# 2225B_VumetreFrequenciel.net
KiCad netlist of a schematic drawn in Altium Designer
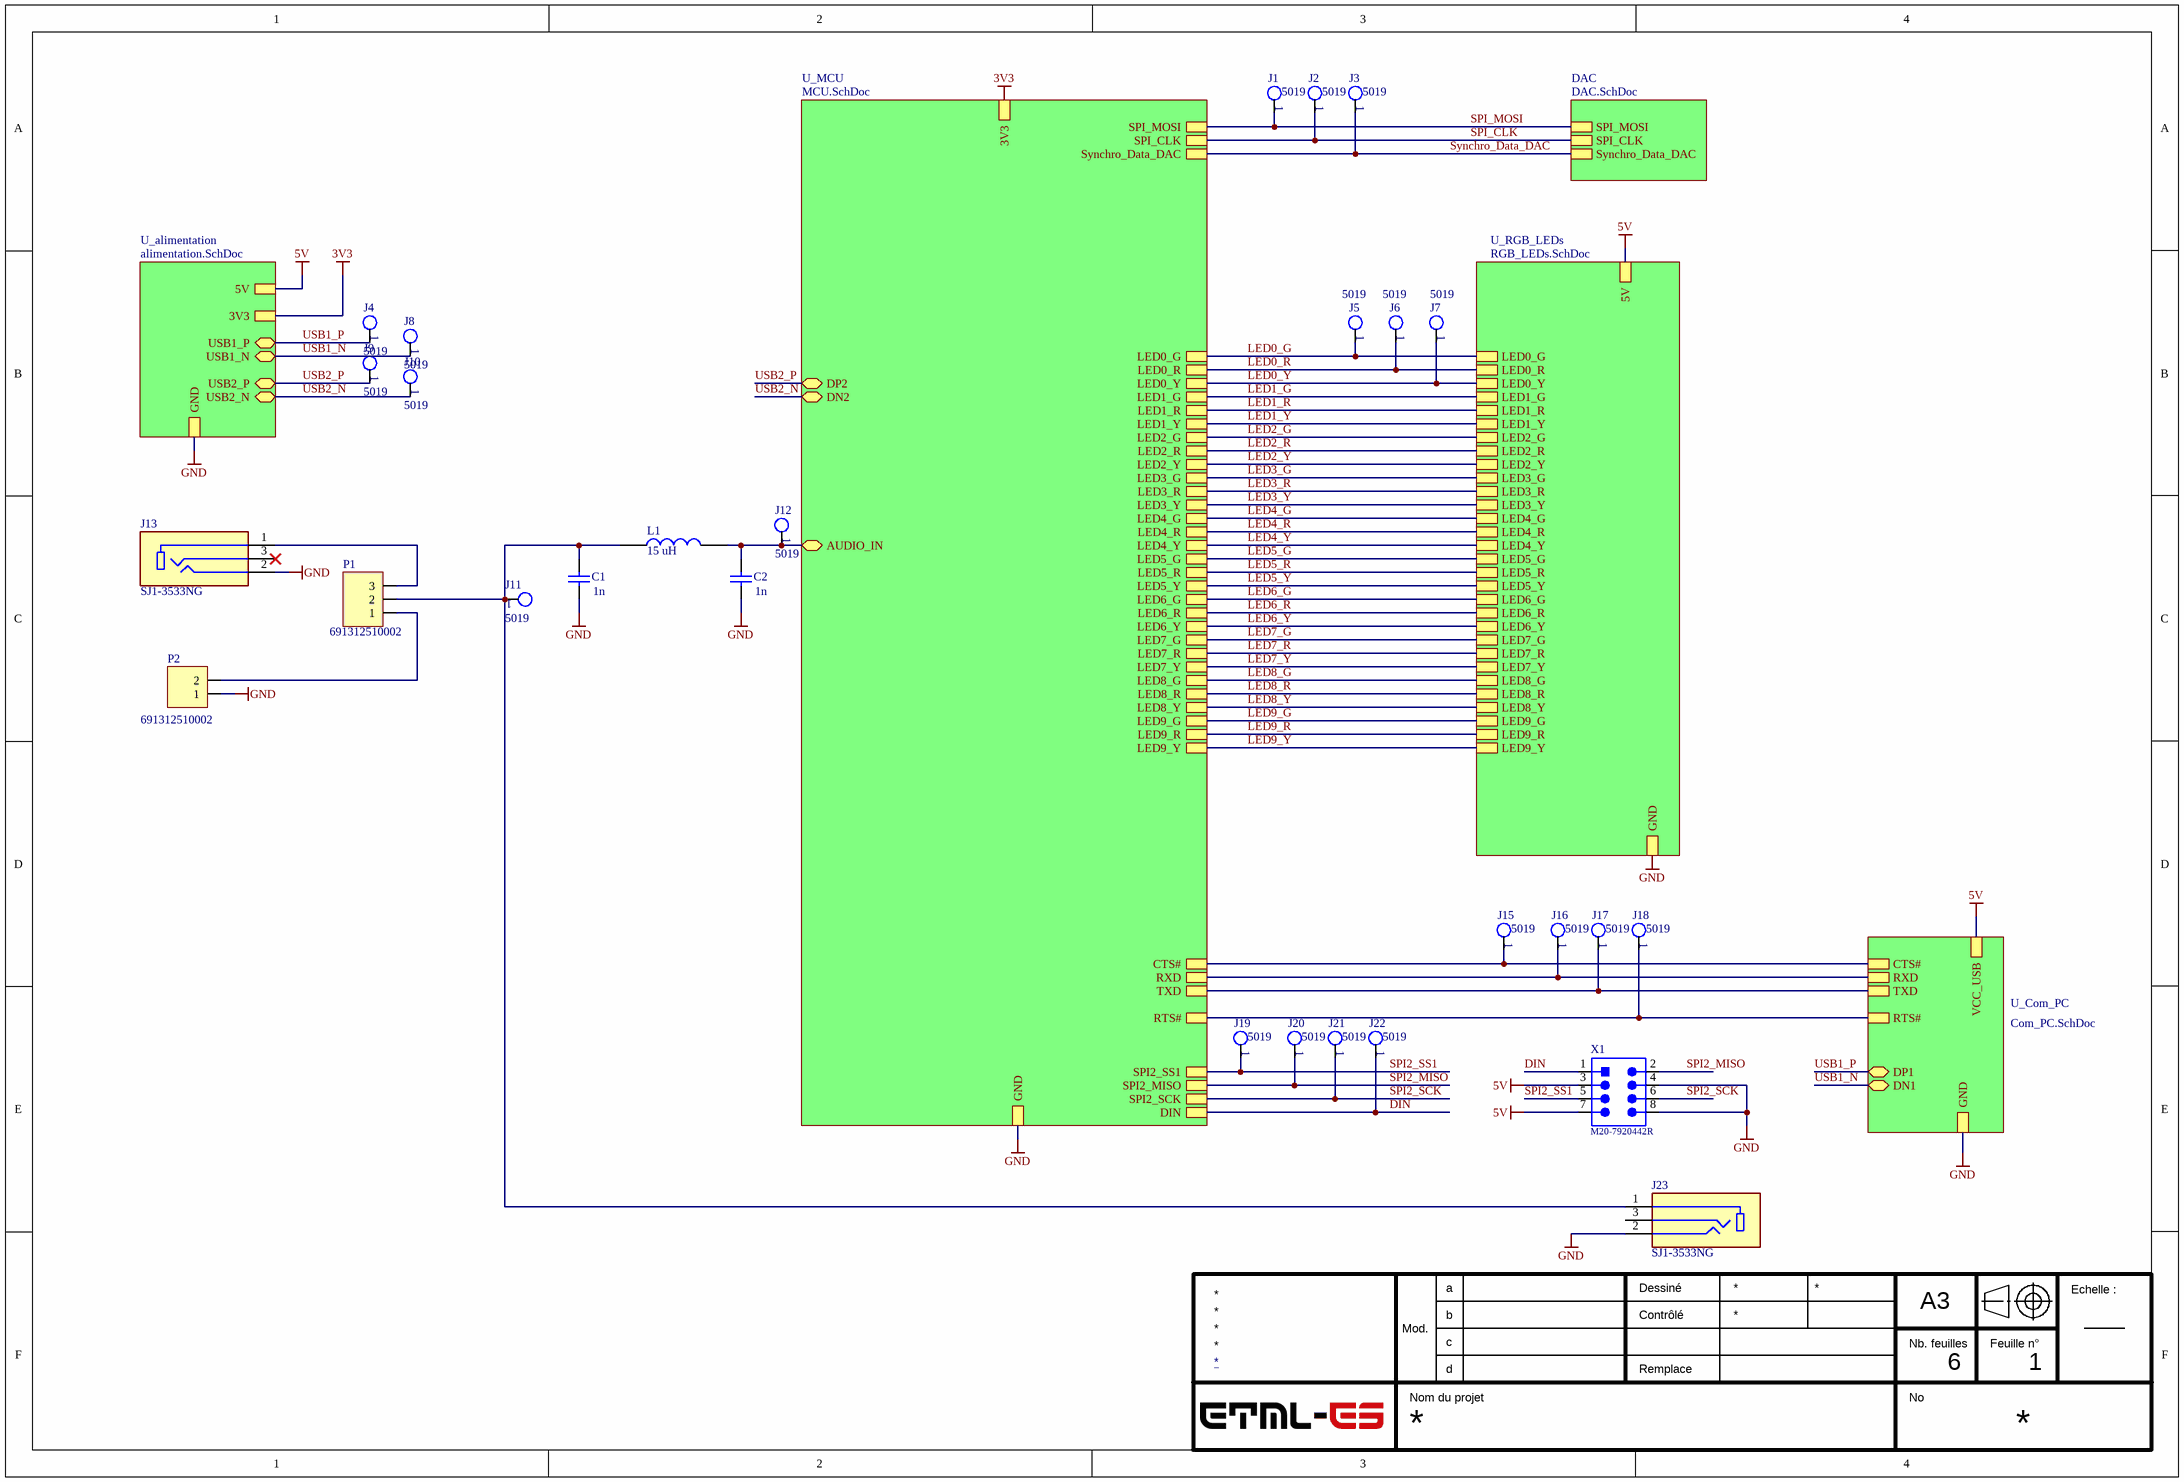
[diagram p0: 2225B_VumetreFrequenciel.SchDoc]

(export (version "E")
  (design (tool "Eeschema 10.0.6"))
  (components
    (comp (ref "C1")
      (value "1n")
      (footprint "C0805")
      (description "Capacitor")
      (fields (field (name "PUBLISHER") "Altium Limited"))
      (libsource (lib "Miscellaneous Devices") (part "Cap"))
    )
    (comp (ref "C2")
      (value "1n")
      (footprint "C0805")
      (description "Capacitor")
      (fields (field (name "PUBLISHER") "Altium Limited"))
      (libsource (lib "Miscellaneous Devices") (part "Cap"))
    )
    (comp (ref "J1")
      (value "5019")
      (footprint "KEYSTONE_5019")
      (fields (field (name "MANUFACTURER") "Keystone Electronics"))
      (libsource (lib "2225B_VumetreFrequenciel") (part "CMP-1672-00008-2"))
    )
    (comp (ref "J2")
      (value "5019")
      (footprint "KEYSTONE_5019")
      (fields (field (name "MANUFACTURER") "Keystone Electronics"))
      (libsource (lib "2225B_VumetreFrequenciel") (part "CMP-1672-00008-2"))
    )
    (comp (ref "J3")
      (value "5019")
      (footprint "KEYSTONE_5019")
      (fields (field (name "MANUFACTURER") "Keystone Electronics"))
      (libsource (lib "2225B_VumetreFrequenciel") (part "CMP-1672-00008-2"))
    )
    (comp (ref "J4")
      (value "5019")
      (footprint "KEYSTONE_5019")
      (fields (field (name "MANUFACTURER") "Keystone Electronics"))
      (libsource (lib "2225B_VumetreFrequenciel") (part "CMP-1672-00008-2"))
    )
    (comp (ref "J5")
      (value "5019")
      (footprint "KEYSTONE_5019")
      (fields (field (name "MANUFACTURER") "Keystone Electronics"))
      (libsource (lib "2225B_VumetreFrequenciel") (part "CMP-1672-00008-2"))
    )
    (comp (ref "J6")
      (value "5019")
      (footprint "KEYSTONE_5019")
      (fields (field (name "MANUFACTURER") "Keystone Electronics"))
      (libsource (lib "2225B_VumetreFrequenciel") (part "CMP-1672-00008-2"))
    )
    (comp (ref "J7")
      (value "5019")
      (footprint "KEYSTONE_5019")
      (fields (field (name "MANUFACTURER") "Keystone Electronics"))
      (libsource (lib "2225B_VumetreFrequenciel") (part "CMP-1672-00008-2"))
    )
    (comp (ref "J8")
      (value "5019")
      (footprint "KEYSTONE_5019")
      (fields (field (name "MANUFACTURER") "Keystone Electronics"))
      (libsource (lib "2225B_VumetreFrequenciel") (part "CMP-1672-00008-2"))
    )
    (comp (ref "J9")
      (value "5019")
      (footprint "KEYSTONE_5019")
      (fields (field (name "MANUFACTURER") "Keystone Electronics"))
      (libsource (lib "2225B_VumetreFrequenciel") (part "CMP-1672-00008-2"))
    )
    (comp (ref "J10")
      (value "5019")
      (footprint "KEYSTONE_5019")
      (fields (field (name "MANUFACTURER") "Keystone Electronics"))
      (libsource (lib "2225B_VumetreFrequenciel") (part "CMP-1672-00008-2"))
    )
    (comp (ref "J11")
      (value "5019")
      (footprint "KEYSTONE_5019")
      (fields (field (name "MANUFACTURER") "Keystone Electronics"))
      (libsource (lib "2225B_VumetreFrequenciel") (part "CMP-1672-00008-2"))
    )
    (comp (ref "J12")
      (value "5019")
      (footprint "KEYSTONE_5019")
      (fields (field (name "MANUFACTURER") "Keystone Electronics"))
      (libsource (lib "2225B_VumetreFrequenciel") (part "CMP-1672-00008-2"))
    )
    (comp (ref "J13")
      (value "SJ1-3533NG")
      (footprint "CUI_SJ1-3533NG")
      (description "3.5 mm Right-Angle Stereo Jack, 3 Pin PCB Mount, Isolated Ground")
      (fields (field (name "MF") "{'manufacturer': u'CUI'}"))
      (libsource (lib "2227_BoiteBruitage") (part "SJ1-3533NG"))
    )
    (comp (ref "J15")
      (value "5019")
      (footprint "KEYSTONE_5019")
      (fields (field (name "MANUFACTURER") "Keystone Electronics"))
      (libsource (lib "2225B_VumetreFrequenciel") (part "CMP-1672-00008-2"))
    )
    (comp (ref "J16")
      (value "5019")
      (footprint "KEYSTONE_5019")
      (fields (field (name "MANUFACTURER") "Keystone Electronics"))
      (libsource (lib "2225B_VumetreFrequenciel") (part "CMP-1672-00008-2"))
    )
    (comp (ref "J17")
      (value "5019")
      (footprint "KEYSTONE_5019")
      (fields (field (name "MANUFACTURER") "Keystone Electronics"))
      (libsource (lib "2225B_VumetreFrequenciel") (part "CMP-1672-00008-2"))
    )
    (comp (ref "J18")
      (value "5019")
      (footprint "KEYSTONE_5019")
      (fields (field (name "MANUFACTURER") "Keystone Electronics"))
      (libsource (lib "2225B_VumetreFrequenciel") (part "CMP-1672-00008-2"))
    )
    (comp (ref "J19")
      (value "5019")
      (footprint "KEYSTONE_5019")
      (fields (field (name "MANUFACTURER") "Keystone Electronics"))
      (libsource (lib "2225B_VumetreFrequenciel") (part "CMP-1672-00008-2"))
    )
    (comp (ref "J20")
      (value "5019")
      (footprint "KEYSTONE_5019")
      (fields (field (name "MANUFACTURER") "Keystone Electronics"))
      (libsource (lib "2225B_VumetreFrequenciel") (part "CMP-1672-00008-2"))
    )
    (comp (ref "J21")
      (value "5019")
      (footprint "KEYSTONE_5019")
      (fields (field (name "MANUFACTURER") "Keystone Electronics"))
      (libsource (lib "2225B_VumetreFrequenciel") (part "CMP-1672-00008-2"))
    )
    (comp (ref "J22")
      (value "5019")
      (footprint "KEYSTONE_5019")
      (fields (field (name "MANUFACTURER") "Keystone Electronics"))
      (libsource (lib "2225B_VumetreFrequenciel") (part "CMP-1672-00008-2"))
    )
    (comp (ref "J23")
      (value "SJ1-3533NG")
      (footprint "CUI_SJ1-3533NG")
      (description "3.5 mm Right-Angle Stereo Jack, 3 Pin PCB Mount, Isolated Ground")
      (fields (field (name "MF") "{'manufacturer': u'CUI'}"))
      (libsource (lib "") (part "SJ1-3533NG_1"))
    )
    (comp (ref "L1")
      (value "15 uH")
      (footprint "WE-PD_1210")
      (description "Fixed Inductors 22uH 2.80A 0.028ohms")
      (fields (field (name "MANUFACTURER_PART_NUMBER") "CDRH125NP-220MC"))
      (libsource (lib "TP2_Convertisseur_Courant") (part "CDRH125NP-220MC"))
    )
    (comp (ref "P1")
      (value "691312510002")
      (footprint "61300311121")
      (description "Header, 3-Pin")
      (fields (field (name "PUBLISHER") "Altium Limited"))
      (libsource (lib "2225B_VumetreFrequenciel") (part "MHDR1X3"))
    )
    (comp (ref "P2")
      (value "691312510002")
      (footprint "LINX_CONBNC002")
      (description "Header, 2-Pin")
      (fields (field (name "PUBLISHER") "Altium Limited"))
      (libsource (lib "2225B_VumetreFrequenciel") (part "MHDR1X2"))
    )
    (comp (ref "X1")
      (value "M20-7920442R")
      (footprint "610108249121")
      (description "WR-PHD Pin Header, THT, pitch 2.54mm, Dual Row, Angled, 8p")
      (fields
        (field (name "MANUFACTURER PART NUMBER") "61300821021")
        (field (name "MANUFACTURER") "Wurth Elektronik")
      )
      (libsource (lib "2126_AffichageMatriciel") (part "610108249121"))
    )
  )
  (nets
    (net (code "1") (name "/AUDIO_IN") (class "Default")
      (node (ref "C2") (pin "1") (pinfunction "1_1") (pintype "passive"))
      (node (ref "J12") (pin "1") (pinfunction "1_1") (pintype "passive"))
      (node (ref "L1") (pin "2") (pinfunction "2_2") (pintype "passive"))
    )
    (net (code "2") (name "/CTS#") (class "Default")
      (node (ref "J15") (pin "1") (pinfunction "1_1") (pintype "passive"))
    )
    (net (code "3") (name "/DIN") (class "Default")
      (node (ref "J22") (pin "1") (pinfunction "1_1") (pintype "passive"))
      (node (ref "X1") (pin "1") (pinfunction "1_1") (pintype "passive"))
    )
    (net (code "4") (name "/LED0_G") (class "Default")
      (node (ref "J5") (pin "1") (pinfunction "1_1") (pintype "passive"))
    )
    (net (code "5") (name "/LED0_R") (class "Default")
      (node (ref "J6") (pin "1") (pinfunction "1_1") (pintype "passive"))
    )
    (net (code "6") (name "/LED0_Y") (class "Default")
      (node (ref "J7") (pin "1") (pinfunction "1_1") (pintype "passive"))
    )
    (net (code "34") (name "/RTS#") (class "Default")
      (node (ref "J18") (pin "1") (pinfunction "1_1") (pintype "passive"))
    )
    (net (code "35") (name "/RXD") (class "Default")
      (node (ref "J16") (pin "1") (pinfunction "1_1") (pintype "passive"))
    )
    (net (code "36") (name "/SPI2_MISO") (class "Default")
      (node (ref "J20") (pin "1") (pinfunction "1_1") (pintype "passive"))
      (node (ref "X1") (pin "2") (pinfunction "2_2") (pintype "passive"))
    )
    (net (code "37") (name "/SPI2_SCK") (class "Default")
      (node (ref "J21") (pin "1") (pinfunction "1_1") (pintype "passive"))
      (node (ref "X1") (pin "6") (pinfunction "6_6") (pintype "passive"))
    )
    (net (code "38") (name "/SPI2_SS1") (class "Default")
      (node (ref "J19") (pin "1") (pinfunction "1_1") (pintype "passive"))
      (node (ref "X1") (pin "5") (pinfunction "5_5") (pintype "passive"))
    )
    (net (code "39") (name "/SPI_CLK") (class "Default")
      (node (ref "J2") (pin "1") (pinfunction "1_1") (pintype "passive"))
    )
    (net (code "40") (name "/SPI_MOSI") (class "Default")
      (node (ref "J1") (pin "1") (pinfunction "1_1") (pintype "passive"))
    )
    (net (code "41") (name "/Synchro_Data_DAC") (class "Default")
      (node (ref "J3") (pin "1") (pinfunction "1_1") (pintype "passive"))
    )
    (net (code "42") (name "/TXD") (class "Default")
      (node (ref "J17") (pin "1") (pinfunction "1_1") (pintype "passive"))
    )
    (net (code "43") (name "/USB1_N") (class "Default")
      (node (ref "J8") (pin "1") (pinfunction "1_1") (pintype "passive"))
    )
    (net (code "44") (name "/USB1_P") (class "Default")
      (node (ref "J4") (pin "1") (pinfunction "1_1") (pintype "passive"))
    )
    (net (code "45") (name "/USB2_N") (class "Default")
      (node (ref "J10") (pin "1") (pinfunction "1_1") (pintype "passive"))
    )
    (net (code "46") (name "/USB2_P") (class "Default")
      (node (ref "J9") (pin "1") (pinfunction "1_1") (pintype "passive"))
    )
    (net (code "48") (name "5V") (class "Default")
      (node (ref "X1") (pin "3") (pinfunction "3_3") (pintype "passive"))
      (node (ref "X1") (pin "7") (pinfunction "7_7") (pintype "passive"))
    )
    (net (code "49") (name "GND") (class "Default")
      (node (ref "C1") (pin "2") (pinfunction "2_2") (pintype "passive"))
      (node (ref "C2") (pin "2") (pinfunction "2_2") (pintype "passive"))
      (node (ref "J13") (pin "2") (pinfunction "2_2") (pintype "passive"))
      (node (ref "J23") (pin "2") (pinfunction "2_2") (pintype "passive"))
      (node (ref "P2") (pin "1") (pinfunction "1_1") (pintype "passive"))
      (node (ref "X1") (pin "4") (pinfunction "4_4") (pintype "passive"))
      (node (ref "X1") (pin "8") (pinfunction "8_8") (pintype "passive"))
    )
    (net (code "50") (name "Net-(C1-Pad1)") (class "Default")
      (node (ref "C1") (pin "1") (pinfunction "1_1") (pintype "passive"))
      (node (ref "J11") (pin "1") (pinfunction "1_1") (pintype "passive"))
      (node (ref "J23") (pin "1") (pinfunction "1_1") (pintype "passive"))
      (node (ref "L1") (pin "1") (pinfunction "1_1") (pintype "passive"))
      (node (ref "P1") (pin "2") (pinfunction "2_2") (pintype "passive"))
    )
    (net (code "51") (name "Net-(J13-Pad1)") (class "Default")
      (node (ref "J13") (pin "1") (pinfunction "1_1") (pintype "passive"))
      (node (ref "P1") (pin "3") (pinfunction "3_3") (pintype "passive"))
    )
    (net (code "52") (name "Net-(P1-Pad1)") (class "Default")
      (node (ref "P1") (pin "1") (pinfunction "1_1") (pintype "passive"))
      (node (ref "P2") (pin "2") (pinfunction "2_2") (pintype "passive"))
    )
    (net (code "53") (name "unconnected-(J13-Pad3)") (class "Default")
      (node (ref "J13") (pin "3") (pinfunction "3_3") (pintype "passive+no_connect"))
    )
    (net (code "54") (name "unconnected-(J23-Pad3)") (class "Default")
      (node (ref "J23") (pin "3") (pinfunction "3_3") (pintype "passive"))
    )
  )
)
